# ArduSensor-Fart.net
KiCad netlist of a schematic drawn in EAGLE
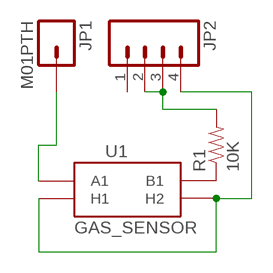
[diagram p0: schematic, sheet 1]

(export (version "E")
  (design (tool "Eeschema 10.0.6"))
  (components
    (comp (ref "JP1")
      (value "M01PTH")
      (footprint "eagle-import:1X01")
      (libsource (lib "eagle-import") (part "M01PTH"))
    )
    (comp (ref "JP2")
      (value "M04PTH")
      (footprint "eagle-import:1X04")
      (libsource (lib "eagle-import") (part "M04PTH"))
    )
    (comp (ref "R1")
      (value "10K")
      (footprint "eagle-import:AXIAL-0.3")
      (libsource (lib "eagle-import") (part "RESISTORAXIAL-0.3"))
    )
    (comp (ref "U1")
      (value "GAS_SENSOR")
      (footprint "eagle-import:MQ-3")
      (libsource (lib "eagle-import") (part "GAS_SENSOR"))
    )
  )
  (nets
    (net (code "1") (name "Net-(JP1-Pad1)") (class "Default")
      (node (ref "JP1") (pin "1") (pinfunction "1_1") (pintype "passive"))
      (node (ref "U1") (pin "A1") (pinfunction "A1_A1") (pintype "bidirectional"))
    )
    (net (code "2") (name "Net-(R1-1)") (class "Default")
      (node (ref "R1") (pin "P$1") (pinfunction "1_P$1") (pintype "passive"))
      (node (ref "U1") (pin "B1") (pinfunction "B1_B1") (pintype "bidirectional"))
    )
    (net (code "3") (name "Net-(R1-2)") (class "Default")
      (node (ref "JP2") (pin "2") (pinfunction "2_2") (pintype "passive"))
      (node (ref "JP2") (pin "3") (pinfunction "3_3") (pintype "passive"))
      (node (ref "R1") (pin "P$2") (pinfunction "2_P$2") (pintype "passive"))
    )
    (net (code "4") (name "Net-(U1-H1)") (class "Default")
      (node (ref "JP2") (pin "4") (pinfunction "4_4") (pintype "passive"))
      (node (ref "U1") (pin "HA") (pinfunction "H1_HA") (pintype "bidirectional"))
      (node (ref "U1") (pin "HB") (pinfunction "H2_HB") (pintype "bidirectional"))
    )
    (net (code "5") (name "unconnected-(JP2-Pad1)") (class "Default")
      (node (ref "JP2") (pin "1") (pinfunction "1_1") (pintype "passive"))
    )
  )
)
